# Power.net
KiCad netlist of a schematic drawn in Altium Designer
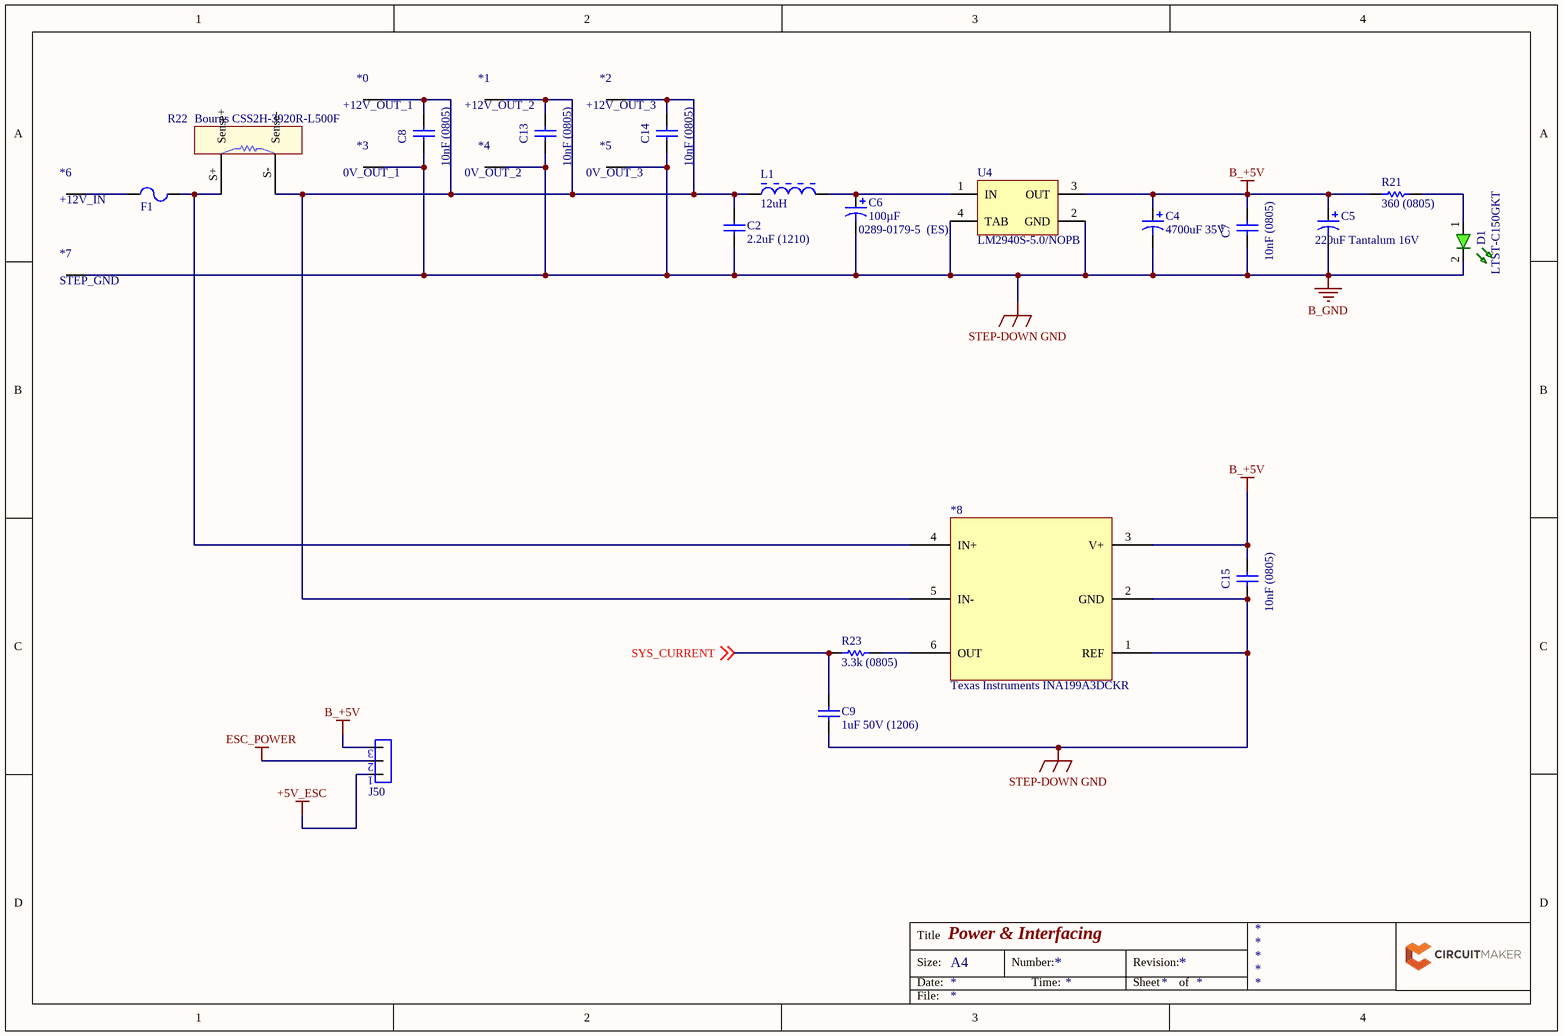
[diagram p0: Power.SchDoc]

(export (version "E")
  (design (tool "Eeschema 10.0.6"))
  (components
    (comp (ref "*0")
      (value "+12V_OUT_1")
      (footprint "PCB-pcj1l6roq5gpi9u538ps-1")
      (description "Standoff; 12 mm; M3 x 0.5; Brass; Hex; Nickel Plate; 8 in.; 8 in.")
      (fields (field (name "MANUFACTURER PART NUMBER") "24314"))
      (libsource (lib "CommunityVault") (part "CMP-5ddc94dc62be821b-2"))
    )
    (comp (ref "*1")
      (value "+12V_OUT_2")
      (footprint "PCB-pcj1l6roq5gpi9u538ps-1")
      (description "Standoff; 12 mm; M3 x 0.5; Brass; Hex; Nickel Plate; 8 in.; 8 in.")
      (fields (field (name "MANUFACTURER PART NUMBER") "24314"))
      (libsource (lib "CommunityVault") (part "CMP-5ddc94dc62be821b-2"))
    )
    (comp (ref "*2")
      (value "+12V_OUT_3")
      (footprint "PCB-pcj1l6roq5gpi9u538ps-1")
      (description "Standoff; 12 mm; M3 x 0.5; Brass; Hex; Nickel Plate; 8 in.; 8 in.")
      (fields (field (name "MANUFACTURER PART NUMBER") "24314"))
      (libsource (lib "CommunityVault") (part "CMP-5ddc94dc62be821b-2"))
    )
    (comp (ref "*3")
      (value "0V_OUT_1")
      (footprint "PCB-pcj1l6roq5gpi9u538ps-1")
      (description "Standoff; 12 mm; M3 x 0.5; Brass; Hex; Nickel Plate; 8 in.; 8 in.")
      (fields (field (name "MANUFACTURER PART NUMBER") "24314"))
      (libsource (lib "CommunityVault") (part "CMP-5ddc94dc62be821b-2"))
    )
    (comp (ref "*4")
      (value "0V_OUT_2")
      (footprint "PCB-pcj1l6roq5gpi9u538ps-1")
      (description "Standoff; 12 mm; M3 x 0.5; Brass; Hex; Nickel Plate; 8 in.; 8 in.")
      (fields (field (name "MANUFACTURER PART NUMBER") "24314"))
      (libsource (lib "CommunityVault") (part "CMP-5ddc94dc62be821b-2"))
    )
    (comp (ref "*5")
      (value "0V_OUT_3")
      (footprint "PCB-pcj1l6roq5gpi9u538ps-1")
      (description "Standoff; 12 mm; M3 x 0.5; Brass; Hex; Nickel Plate; 8 in.; 8 in.")
      (fields (field (name "MANUFACTURER PART NUMBER") "24314"))
      (libsource (lib "CommunityVault") (part "CMP-5ddc94dc62be821b-2"))
    )
    (comp (ref "*6")
      (value "+12V_IN")
      (footprint "PCB-pcj1l6roq5gpi9u538ps-1")
      (description "Standoff; 12 mm; M3 x 0.5; Brass; Hex; Nickel Plate; 8 in.; 8 in.")
      (fields (field (name "MANUFACTURER PART NUMBER") "24314"))
      (libsource (lib "CommunityVault") (part "CMP-5ddc94dc62be821b-2"))
    )
    (comp (ref "*7")
      (value "STEP_GND")
      (footprint "PCB-pcj1l6roq5gpi9u538ps-1")
      (description "Standoff; 12 mm; M3 x 0.5; Brass; Hex; Nickel Plate; 8 in.; 8 in.")
      (fields (field (name "MANUFACTURER PART NUMBER") "24314"))
      (libsource (lib "CommunityVault") (part "CMP-5ddc94dc62be821b-2"))
    )
    (comp (ref "*8")
      (value "Texas Instruments INA199A3DCKR")
      (footprint "PCB-77zgin3zajz1p7ole171-1")
      (fields (field (name "MANUFACTURER PART NUMBER") "INA199A3DCKR"))
      (libsource (lib "FavoritesLibrary") (part "SYM-6ab6a2a7a250b571-1"))
    )
    (comp (ref "C2")
      (value "2.2uF (1210)")
      (footprint "PCB-2fbb0vau3p468w0y920g-1")
      (description "1210 4.7 uF 50 V ±10% Tolerance X7R SMT Multilayer Ceramic Capacitor")
      (fields (field (name "MANUFACTURER PART NUMBER") "GRM32ER71H475KA88L"))
      (libsource (lib "FavoritesLibrary") (part "SYM-8d884480570e524f-1"))
    )
    (comp (ref "C4")
      (value "4700uF 35V")
      (footprint "PCB-uagykt4yf5hbq2so0sas-1")
      (description "18mm x 40mm l/s=7.5mm 105deg 4700uf 35v Radial Leads Lesr Aluminum Electrolytic Cap")
      (fields (field (name "MANUFACTURER PART NUMBER") "UPW1V472MHD"))
      (libsource (lib "FavoritesLibrary") (part "SYM-4cda85d37137931d-1"))
    )
    (comp (ref "C5")
      (value "220uF Tantalum 16V")
      (footprint "PCB-fa1e6qpy6fbu77u2ye0h-1")
      (fields (field (name "MANUFACTURER PART NUMBER") "T491E227K016AT"))
      (libsource (lib "FavoritesLibrary") (part "SYM-d5771c7fde4f0ab0-1"))
    )
    (comp (ref "C6")
      (value "100µF")
      (footprint "PCB-ec5i0bi6g8n3i6bd77c9-1")
      (description "WX Series 100 uF 25 V ±20 % Surface Mount Chip Aluminum Electrolytic Capacitor")
      (fields (field (name "OCTOPARTID") "0289-0179-5  (ES)"))
      (libsource (lib "CommunityVault") (part "CMP-42da8bd37ecc9d1d-1"))
    )
    (comp (ref "C7")
      (value "10nF (0805)")
      (footprint "CAPC2013X94X50NL20T25")
      (description "CAP CER 10NF 50V 5% X7R 0805")
      (fields (field (name "MANUFACTURER PART NUMBER") "08055C103JAT2A"))
      (libsource (lib "FavoritesLibrary") (part "CAP-2"))
    )
    (comp (ref "C8")
      (value "10nF (0805)")
      (footprint "CAPC2013X94X50NL20T25")
      (description "CAP CER 10NF 50V 5% X7R 0805")
      (fields (field (name "MANUFACTURER PART NUMBER") "08055C103JAT2A"))
      (libsource (lib "FavoritesLibrary") (part "CAP-2"))
    )
    (comp (ref "C9")
      (value "1uF 50V (1206)")
      (footprint "CAPC3216X180X55NL20T25")
      (description "CAP CER 1UF 50V 10% X7R 1206")
      (libsource (lib "FavoritesLibrary") (part "CAP-2"))
    )
    (comp (ref "C13")
      (value "10nF (0805)")
      (footprint "CAPC2013X94X50NL20T25")
      (description "CAP CER 10NF 50V 5% X7R 0805")
      (fields (field (name "MANUFACTURER PART NUMBER") "08055C103JAT2A"))
      (libsource (lib "FavoritesLibrary") (part "CAP-2"))
    )
    (comp (ref "C14")
      (value "10nF (0805)")
      (footprint "CAPC2013X94X50NL20T25")
      (description "CAP CER 10NF 50V 5% X7R 0805")
      (fields (field (name "MANUFACTURER PART NUMBER") "08055C103JAT2A"))
      (libsource (lib "FavoritesLibrary") (part "CAP-2"))
    )
    (comp (ref "C15")
      (value "10nF (0805)")
      (footprint "CAPC2013X94X50NL20T25")
      (description "CAP CER 10NF 50V 5% X7R 0805")
      (fields (field (name "MANUFACTURER PART NUMBER") "08055C103JAT2A"))
      (libsource (lib "FavoritesLibrary") (part "CAP-2"))
    )
    (comp (ref "D1")
      (value "Lite-On LTST-C150GKT")
      (footprint "PCB-ol758qabjjwuqvqjb2k1-1")
      (description "Green 3.2 x 1.6 x 1.1 mm 130° Water Clear 6 mcd 2.1 V Chip LED Surface Mount")
      (fields
        (field (name "MANUFACTURER") "LITE-ON")
        (field (name "MANUFACTURER PART NUMBER") "LTST-C150GKT")
      )
      (libsource (lib "FavoritesLibrary") (part "LED, GREEN 1206"))
    )
    (comp (ref "F1")
      (value "Keystone 3544-2")
      (footprint "PCB-p3yqezitk9kmwwp2mp00-1")
      (description "Fuse Clip; 500 VAC; 30 A; PCB; For 0.110 in. x 0.032 in. mini blade fuses")
      (fields (field (name "MANUFACTURER PART NUMBER") "3544-2"))
      (libsource (lib "CommunityVault") (part "CMP-54019d0b3e378bc6-3"))
    )
    (comp (ref "J50")
      (value "TE Connectivity / AMP 5-146274-3")
      (footprint "PCB-m19gj7kkh000buv4lmik-1")
      (description "AMPMODU 3 Position 2.54 mm Single Row Through-Hole Straight Breakaway Header")
      (fields (field (name "MANUFACTURER PART NUMBER") "5-146274-3"))
      (libsource (lib "FavoritesLibrary") (part "SYM-52d299a8d8748d15-1"))
    )
    (comp (ref "L1")
      (value "12uH")
      (footprint "BOUR-SDR0403-2_V")
      (libsource (lib "FavoritesLibrary") (part "BOUR-IND-2A"))
    )
    (comp (ref "R21")
      (value "360 (0805)")
      (footprint "RESC2013X60X40NL15T20")
      (description "RES SMD 10K OHM 1% 1/3W 0805")
      (libsource (lib "CommunityVault") (part "CMP-1860549-2"))
    )
    (comp (ref "R22")
      (value "Bourns CSS2H-3920R-L500F")
      (footprint "PCB-p7sd064g1v6dorbgawsb-1")
      (description "Res Metal Strip 3920 0.0005 Ohm 1% 9W ±50ppm/C Pad SMD Automotive T/R")
      (fields (field (name "MANUFACTURER PART NUMBER") "CSS2H-3920R-L500F"))
      (libsource (lib "FavoritesLibrary") (part "SYM-5a03976e567885c4-1"))
    )
    (comp (ref "R23")
      (value "3.3k (0805)")
      (footprint "RESC2013X60X40NL15T20")
      (description "RES SMD 10K OHM 1% 1/3W 0805")
      (libsource (lib "CommunityVault") (part "CMP-1860549-2"))
    )
    (comp (ref "U4")
      (value "LM2940S-5.0/NOPB")
      (footprint "TS3B_L")
      (description "1A Low Dropout Regulator, 3-pin TO-263, Pb-Free")
      (libsource (lib "FavoritesLibrary") (part "PM-REG-LM2940-TO4"))
    )
  )
  (nets
    (net (code "1") (name "+5V_ESC") (class "Default")
      (node (ref "J50") (pin "1") (pinfunction "1_1") (pintype "passive"))
    )
    (net (code "2") (name "B_+5V") (class "Default")
      (node (ref "*8") (pin "3") (pinfunction "V+_3") (pintype "passive"))
      (node (ref "C15") (pin "2") (pinfunction "2_2") (pintype "passive"))
      (node (ref "C4") (pin "1") (pinfunction "1_1") (pintype "passive"))
      (node (ref "C5") (pin "1") (pinfunction "1_1") (pintype "passive"))
      (node (ref "C7") (pin "2") (pinfunction "2_2") (pintype "passive"))
      (node (ref "J50") (pin "3") (pinfunction "3_3") (pintype "passive"))
      (node (ref "R21") (pin "1") (pinfunction "1_1") (pintype "passive"))
      (node (ref "U4") (pin "3") (pinfunction "OUT_3") (pintype "power_in"))
    )
    (net (code "3") (name "B_GND") (class "Default")
      (node (ref "*3") (pin "0") (pinfunction "0_0") (pintype "power_in"))
      (node (ref "*4") (pin "0") (pinfunction "0_0") (pintype "power_in"))
      (node (ref "*5") (pin "0") (pinfunction "0_0") (pintype "power_in"))
      (node (ref "*7") (pin "0") (pinfunction "0_0") (pintype "power_in"))
      (node (ref "*8") (pin "1") (pinfunction "REF_1") (pintype "passive"))
      (node (ref "*8") (pin "2") (pinfunction "GND_2") (pintype "passive"))
      (node (ref "C13") (pin "1") (pinfunction "1_1") (pintype "passive"))
      (node (ref "C14") (pin "1") (pinfunction "1_1") (pintype "passive"))
      (node (ref "C15") (pin "1") (pinfunction "1_1") (pintype "passive"))
      (node (ref "C2") (pin "1") (pinfunction "1_1") (pintype "passive"))
      (node (ref "C4") (pin "2") (pinfunction "2_2") (pintype "passive"))
      (node (ref "C5") (pin "2") (pinfunction "2_2") (pintype "passive"))
      (node (ref "C6") (pin "2") (pinfunction "2_2") (pintype "passive"))
      (node (ref "C7") (pin "1") (pinfunction "1_1") (pintype "passive"))
      (node (ref "C8") (pin "1") (pinfunction "1_1") (pintype "passive"))
      (node (ref "C9") (pin "1") (pinfunction "1_1") (pintype "passive"))
      (node (ref "D1") (pin "2") (pinfunction "K_2") (pintype "passive"))
      (node (ref "U4") (pin "2") (pinfunction "GND_2") (pintype "power_in"))
      (node (ref "U4") (pin "4") (pinfunction "TAB_4") (pintype "power_in"))
    )
    (net (code "4") (name "ESC_POWER") (class "Default")
      (node (ref "J50") (pin "2") (pinfunction "2_2") (pintype "passive"))
    )
    (net (code "5") (name "Net-(*6-Pad0)") (class "Default")
      (node (ref "*6") (pin "0") (pinfunction "0_0") (pintype "power_in"))
      (node (ref "F1") (pin "1") (pinfunction "1_1") (pintype "passive"))
    )
    (net (code "6") (name "Net-(*8-IN+)") (class "Default")
      (node (ref "*8") (pin "4") (pinfunction "IN+_4") (pintype "passive"))
      (node (ref "F1") (pin "2") (pinfunction "2_2") (pintype "passive"))
      (node (ref "R22") (pin "S+") (pinfunction "Sense+_S+") (pintype "passive"))
    )
    (net (code "7") (name "Net-(*8-IN-)") (class "Default")
      (node (ref "*0") (pin "0") (pinfunction "0_0") (pintype "power_in"))
      (node (ref "*1") (pin "0") (pinfunction "0_0") (pintype "power_in"))
      (node (ref "*2") (pin "0") (pinfunction "0_0") (pintype "power_in"))
      (node (ref "*8") (pin "5") (pinfunction "IN-_5") (pintype "passive"))
      (node (ref "C13") (pin "2") (pinfunction "2_2") (pintype "passive"))
      (node (ref "C14") (pin "2") (pinfunction "2_2") (pintype "passive"))
      (node (ref "C2") (pin "2") (pinfunction "2_2") (pintype "passive"))
      (node (ref "C8") (pin "2") (pinfunction "2_2") (pintype "passive"))
      (node (ref "L1") (pin "1") (pinfunction "1_1") (pintype "passive"))
      (node (ref "R22") (pin "S-") (pinfunction "Sense-_S-") (pintype "passive"))
    )
    (net (code "8") (name "Net-(*8-OUT)") (class "Default")
      (node (ref "*8") (pin "6") (pinfunction "OUT_6") (pintype "passive"))
      (node (ref "R23") (pin "1") (pinfunction "1_1") (pintype "passive"))
    )
    (net (code "9") (name "Net-(D1-A)") (class "Default")
      (node (ref "D1") (pin "1") (pinfunction "A_1") (pintype "passive"))
      (node (ref "R21") (pin "2") (pinfunction "2_2") (pintype "passive"))
    )
    (net (code "10") (name "Net-(U4-IN)") (class "Default")
      (node (ref "C6") (pin "1") (pinfunction "1_1") (pintype "passive"))
      (node (ref "L1") (pin "2") (pinfunction "2_2") (pintype "passive"))
      (node (ref "U4") (pin "1") (pinfunction "IN_1") (pintype "power_in"))
    )
    (net (code "11") (name "SYS_CURRENT") (class "Default")
      (node (ref "C9") (pin "2") (pinfunction "2_2") (pintype "passive"))
      (node (ref "R23") (pin "2") (pinfunction "2_2") (pintype "passive"))
    )
  )
)
